# ADP1612_Boost_Converter.net
KiCad netlist of a schematic drawn in EAGLE
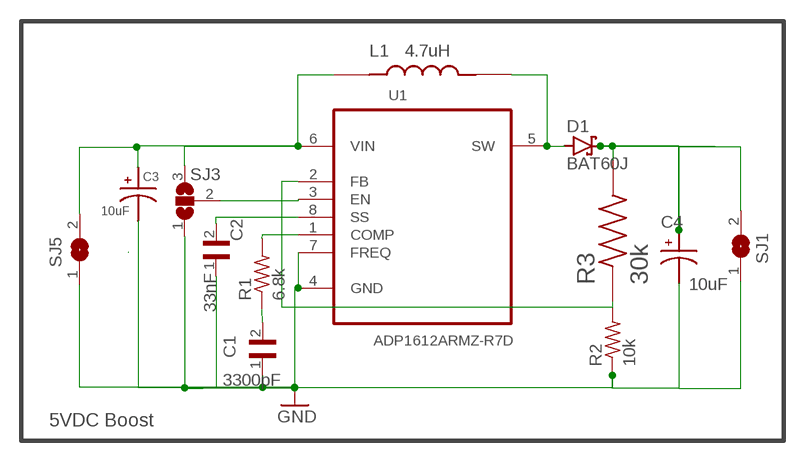
[diagram p0: schematic, sheet 1]

(export (version "E")
  (design (tool "Eeschema 10.0.6"))
  (components
    (comp (ref "C1")
      (value "3300pF")
      (footprint "eagle-import:CAPC0603X33N")
      (fields (field (name "MF") "Murata") (field (name "MP") "GRM033R71E332KA12J"))
      (libsource (lib "eagle-import") (part "GRM033R71E332KA12J"))
    )
    (comp (ref "C2")
      (value "33nF")
      (footprint "eagle-import:CAPC2012X95N")
      (fields (field (name "MF") "Murata") (field (name "MP") "GCM219R71H334KA55J"))
      (libsource (lib "eagle-import") (part "GCM219R71H334KA55J"))
    )
    (comp (ref "C3")
      (value "10uF")
      (footprint "eagle-import:CAPAE430X550N")
      (fields (field (name "MF") "Panasonic") (field (name "MP") "EEE-1CA100SR"))
      (libsource (lib "eagle-import") (part "EEE-1CA100SR"))
    )
    (comp (ref "C4")
      (value "10uF")
      (footprint "eagle-import:CAPAE430X550N")
      (fields (field (name "MF") "Panasonic") (field (name "MP") "EEE-1CA100SR"))
      (libsource (lib "eagle-import") (part "EEE-1CA100SR"))
    )
    (comp (ref "D1")
      (value "BAT60J")
      (footprint "eagle-import:SOD323_ST")
      (libsource (lib "eagle-import") (part "BAT60J"))
    )
    (comp (ref "L1")
      (value "4.7uH")
      (footprint "eagle-import:IND_LQH43NZ4R7M03L")
      (fields (field (name "MF") "Murata") (field (name "MP") "LQH43NZ4R7M03L"))
      (libsource (lib "eagle-import") (part "LQH43NZ4R7M03L"))
    )
    (comp (ref "R1")
      (value "6.8k")
      (footprint "eagle-import:RESC2012X65N")
      (fields (field (name "MF") "TE Connectivity") (field (name "MP") "RP73PF2A10KBTDF"))
      (libsource (lib "eagle-import") (part "RP73PF2A10KBTDF"))
    )
    (comp (ref "R2")
      (value "10k")
      (footprint "eagle-import:RESC2012X65N")
      (fields (field (name "MF") "TE Connectivity") (field (name "MP") "RP73PF2A10KBTDF"))
      (libsource (lib "eagle-import") (part "RP73PF2A10KBTDF"))
    )
    (comp (ref "R3")
      (value "30k")
      (footprint "eagle-import:RESC6332X65N")
      (fields
        (field (name "COMMENT") "8-2176070-4")
        (field (name "MF") "TE Connectivity")
        (field (name "MP") "352130KFT")
      )
      (libsource (lib "eagle-import") (part "352130KFT"))
    )
    (comp (ref "SJ1")
      (value "SJW")
      (footprint "eagle-import:SJW")
      (libsource (lib "eagle-import") (part "SJW"))
    )
    (comp (ref "SJ3")
      (value "SJ2WW")
      (footprint "eagle-import:SJ_2W")
      (libsource (lib "eagle-import") (part "SJ2WW"))
    )
    (comp (ref "SJ5")
      (value "SJW")
      (footprint "eagle-import:SJW")
      (libsource (lib "eagle-import") (part "SJW"))
    )
    (comp (ref "U1")
      (value "ADP1612ARMZ-R7D")
      (footprint "eagle-import:SOIC-08")
      (fields (field (name "MF") "Analog Devices") (field (name "MP") "ADP1612ARMZ-R7"))
      (libsource (lib "eagle-import") (part "ADP1612ARMZ-R7D"))
    )
  )
  (nets
    (net (code "1") (name "GND") (class "Default")
      (node (ref "C1") (pin "1") (pinfunction "1_1") (pintype "passive"))
      (node (ref "C2") (pin "1") (pinfunction "1_1") (pintype "passive"))
      (node (ref "C3") (pin "2") (pinfunction "2_2") (pintype "passive"))
      (node (ref "C4") (pin "2") (pinfunction "2_2") (pintype "passive"))
      (node (ref "R2") (pin "1") (pinfunction "1_1") (pintype "passive"))
      (node (ref "SJ1") (pin "1") (pinfunction "1_1") (pintype "passive"))
      (node (ref "SJ3") (pin "1") (pinfunction "1_1") (pintype "passive"))
      (node (ref "SJ5") (pin "1") (pinfunction "1_1") (pintype "passive"))
      (node (ref "U1") (pin "4") (pinfunction "GND_4") (pintype "passive"))
      (node (ref "U1") (pin "7") (pinfunction "FREQ_7") (pintype "input"))
    )
    (net (code "2") (name "Net-(C1-Pad2)") (class "Default")
      (node (ref "C1") (pin "2") (pinfunction "2_2") (pintype "passive"))
      (node (ref "R1") (pin "1") (pinfunction "1_1") (pintype "passive"))
    )
    (net (code "3") (name "Net-(C4-Pad1)") (class "Default")
      (node (ref "C4") (pin "1") (pinfunction "1_1") (pintype "passive"))
      (node (ref "D1") (pin "C") (pinfunction "C_C") (pintype "passive"))
      (node (ref "R3") (pin "2") (pinfunction "2_2") (pintype "passive"))
      (node (ref "SJ1") (pin "2") (pinfunction "2_2") (pintype "passive"))
    )
    (net (code "4") (name "Net-(U1-COMP)") (class "Default")
      (node (ref "R1") (pin "2") (pinfunction "2_2") (pintype "passive"))
      (node (ref "U1") (pin "1") (pinfunction "COMP_1") (pintype "passive"))
    )
    (net (code "5") (name "Net-(U1-EN)") (class "Default")
      (node (ref "SJ3") (pin "2") (pinfunction "2_2") (pintype "passive"))
      (node (ref "U1") (pin "3") (pinfunction "EN_3") (pintype "input"))
    )
    (net (code "6") (name "Net-(U1-FB)") (class "Default")
      (node (ref "R2") (pin "2") (pinfunction "2_2") (pintype "passive"))
      (node (ref "R3") (pin "1") (pinfunction "1_1") (pintype "passive"))
      (node (ref "U1") (pin "2") (pinfunction "FB_2") (pintype "input"))
    )
    (net (code "7") (name "Net-(U1-SS)") (class "Default")
      (node (ref "C2") (pin "2") (pinfunction "2_2") (pintype "passive"))
      (node (ref "U1") (pin "8") (pinfunction "SS_8") (pintype "input"))
    )
    (net (code "8") (name "Net-(U1-SW)") (class "Default")
      (node (ref "D1") (pin "A") (pinfunction "A_A") (pintype "passive"))
      (node (ref "L1") (pin "2") (pinfunction "2_2") (pintype "passive"))
      (node (ref "U1") (pin "5") (pinfunction "SW_5") (pintype "output"))
    )
    (net (code "9") (name "Net-(U1-VIN)") (class "Default")
      (node (ref "C3") (pin "1") (pinfunction "1_1") (pintype "passive"))
      (node (ref "L1") (pin "1") (pinfunction "1_1") (pintype "passive"))
      (node (ref "SJ3") (pin "3") (pinfunction "3_3") (pintype "passive"))
      (node (ref "SJ5") (pin "2") (pinfunction "2_2") (pintype "passive"))
      (node (ref "U1") (pin "6") (pinfunction "VIN_6") (pintype "input"))
    )
  )
)
